# cdh.net
KiCad netlist of a schematic drawn in Altium Designer
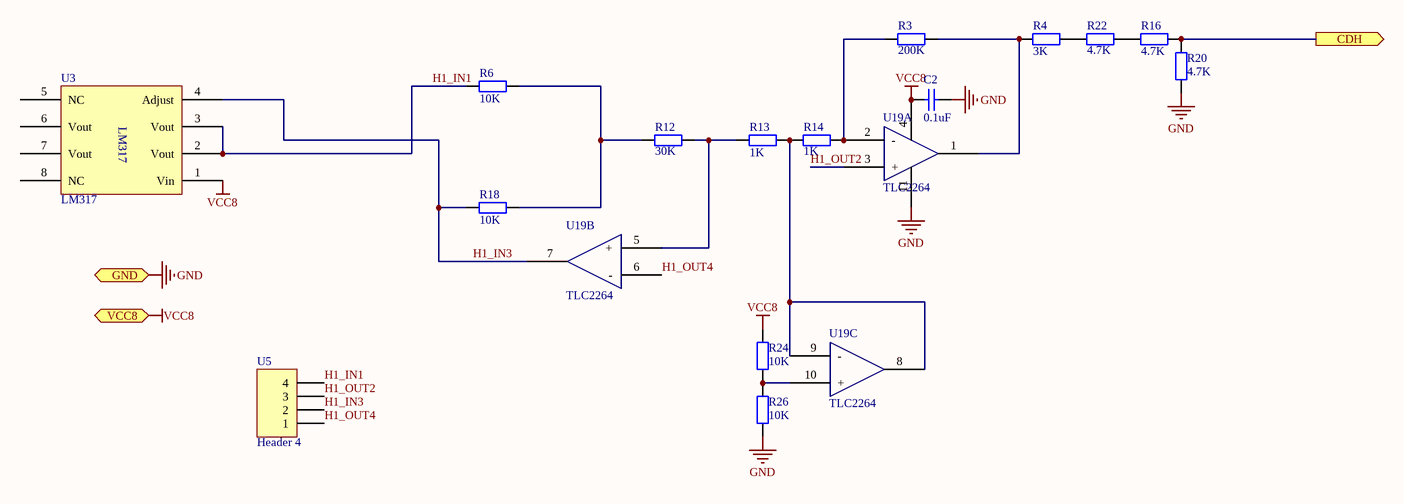
[diagram p0: cdh.SchDoc]

(export (version "E")
  (design (tool "Eeschema 10.0.6"))
  (components
    (comp (ref "C2")
      (value "0.1uF")
      (footprint "C0805")
      (description "Capacitor (Semiconductor SIM Model)")
      (fields (field (name "PUBLISHER") "Altium Limited"))
      (libsource (lib "Miscellaneous Devices") (part "Cap Semi"))
    )
    (comp (ref "R3")
      (value "200K")
      (footprint "0603_R")
      (description "Resistor")
      (fields (field (name "PUBLISHER") "Altium Limited"))
      (libsource (lib "") (part "Res2_1"))
    )
    (comp (ref "R4")
      (value "3K")
      (footprint "0603_R")
      (description "Resistor")
      (fields (field (name "PUBLISHER") "Altium Limited"))
      (libsource (lib "") (part "Res2_1"))
    )
    (comp (ref "R6")
      (value "10K")
      (footprint "0603_R")
      (description "Resistor")
      (fields (field (name "PUBLISHER") "Altium Limited"))
      (libsource (lib "") (part "Res2_1"))
    )
    (comp (ref "R12")
      (value "30K")
      (footprint "0603_R")
      (description "Resistor")
      (fields (field (name "PUBLISHER") "Altium Limited"))
      (libsource (lib "") (part "Res2_1"))
    )
    (comp (ref "R13")
      (value "1K")
      (footprint "0603_R")
      (description "Resistor")
      (fields (field (name "PUBLISHER") "Altium Limited"))
      (libsource (lib "") (part "Res2_1"))
    )
    (comp (ref "R14")
      (value "1K")
      (footprint "0603_R")
      (description "Resistor")
      (fields (field (name "PUBLISHER") "Altium Limited"))
      (libsource (lib "") (part "Res2_2"))
    )
    (comp (ref "R16")
      (value "4.7K")
      (footprint "0603_R")
      (description "Resistor")
      (fields (field (name "PUBLISHER") "Altium Limited"))
      (libsource (lib "") (part "Res2_1"))
    )
    (comp (ref "R18")
      (value "10K")
      (footprint "0603_R")
      (description "Resistor")
      (fields (field (name "PUBLISHER") "Altium Limited"))
      (libsource (lib "") (part "Res2_1"))
    )
    (comp (ref "R20")
      (value "4.7K")
      (footprint "0603_R")
      (description "Resistor")
      (fields (field (name "PUBLISHER") "Altium Limited"))
      (libsource (lib "Miscellaneous Devices") (part "Res2"))
    )
    (comp (ref "R22")
      (value "4.7K")
      (footprint "0603_R")
      (description "Resistor")
      (fields (field (name "PUBLISHER") "Altium Limited"))
      (libsource (lib "") (part "Res2_1"))
    )
    (comp (ref "R24")
      (value "10K")
      (footprint "0603_R")
      (description "Resistor")
      (fields (field (name "PUBLISHER") "Altium Limited"))
      (libsource (lib "Miscellaneous Devices") (part "Res2"))
    )
    (comp (ref "R26")
      (value "10K")
      (footprint "0603_R")
      (description "Resistor")
      (fields (field (name "PUBLISHER") "Altium Limited"))
      (libsource (lib "Miscellaneous Devices") (part "Res2"))
    )
    (comp (ref "U3") (value "LM317") (footprint "SO-8") (libsource (lib "磁导航") (part "LM317")))
    (comp (ref "U5")
      (value "Header 4")
      (footprint "PIN4")
      (description "Header, 4-Pin")
      (fields (field (name "PUBLISHER") "Altium Limited"))
      (libsource (lib "Miscellaneous Connectors") (part "Header 4"))
    )
    (comp (ref "U19") (value "TLC2264") (footprint "TSSOP14") (libsource (lib "EXPLORER") (part "TLC2264")))
  )
  (nets
    (net (code "1") (name "/CDH") (class "Default")
      (node (ref "R16") (pin "2") (pinfunction "2_2") (pintype "passive"))
      (node (ref "R20") (pin "2") (pinfunction "2_2") (pintype "passive"))
    )
    (net (code "2") (name "/H1_IN1") (class "Default")
      (node (ref "R6") (pin "1") (pinfunction "1_1") (pintype "passive"))
      (node (ref "U3") (pin "2") (pinfunction "Vout_2") (pintype "passive"))
      (node (ref "U3") (pin "3") (pinfunction "Vout_3") (pintype "passive"))
      (node (ref "U5") (pin "4") (pinfunction "4_4") (pintype "passive"))
    )
    (net (code "3") (name "/H1_IN3") (class "Default")
      (node (ref "R18") (pin "1") (pinfunction "1_1") (pintype "passive"))
      (node (ref "U19") (pin "7") (pinfunction "2OUT_7") (pintype "passive"))
      (node (ref "U3") (pin "4") (pinfunction "Adjust_4") (pintype "passive"))
      (node (ref "U5") (pin "2") (pinfunction "2_2") (pintype "passive"))
    )
    (net (code "4") (name "/H1_OUT2") (class "Default")
      (node (ref "U19") (pin "3") (pinfunction "+_3") (pintype "passive"))
      (node (ref "U5") (pin "3") (pinfunction "3_3") (pintype "passive"))
    )
    (net (code "5") (name "/H1_OUT4") (class "Default")
      (node (ref "U19") (pin "6") (pinfunction "-_6") (pintype "passive"))
      (node (ref "U5") (pin "1") (pinfunction "1_1") (pintype "passive"))
    )
    (net (code "6") (name "GND") (class "Default")
      (node (ref "C2") (pin "1") (pinfunction "1_1") (pintype "passive"))
      (node (ref "R20") (pin "1") (pinfunction "1_1") (pintype "passive"))
      (node (ref "R26") (pin "1") (pinfunction "1_1") (pintype "passive"))
      (node (ref "U19") (pin "11") (pinfunction "GND_11") (pintype "passive"))
    )
    (net (code "7") (name "Net-(R12-Pad1)") (class "Default")
      (node (ref "R12") (pin "1") (pinfunction "1_1") (pintype "passive"))
      (node (ref "R18") (pin "2") (pinfunction "2_2") (pintype "passive"))
      (node (ref "R6") (pin "2") (pinfunction "2_2") (pintype "passive"))
    )
    (net (code "8") (name "Net-(R16-Pad1)") (class "Default")
      (node (ref "R16") (pin "1") (pinfunction "1_1") (pintype "passive"))
      (node (ref "R22") (pin "2") (pinfunction "2_2") (pintype "passive"))
    )
    (net (code "9") (name "Net-(R22-Pad1)") (class "Default")
      (node (ref "R22") (pin "1") (pinfunction "1_1") (pintype "passive"))
      (node (ref "R4") (pin "2") (pinfunction "2_2") (pintype "passive"))
    )
    (net (code "10") (name "Net-(U19A--)") (class "Default")
      (node (ref "R14") (pin "1") (pinfunction "1_1") (pintype "passive"))
      (node (ref "R3") (pin "1") (pinfunction "1_1") (pintype "passive"))
      (node (ref "U19") (pin "2") (pinfunction "-_2") (pintype "passive"))
    )
    (net (code "11") (name "Net-(U19A-1OUT)") (class "Default")
      (node (ref "R3") (pin "2") (pinfunction "2_2") (pintype "passive"))
      (node (ref "R4") (pin "1") (pinfunction "1_1") (pintype "passive"))
      (node (ref "U19") (pin "1") (pinfunction "1OUT_1") (pintype "passive"))
    )
    (net (code "12") (name "Net-(U19B-+)") (class "Default")
      (node (ref "R12") (pin "2") (pinfunction "2_2") (pintype "passive"))
      (node (ref "R13") (pin "1") (pinfunction "1_1") (pintype "passive"))
      (node (ref "U19") (pin "5") (pinfunction "+_5") (pintype "passive"))
    )
    (net (code "13") (name "Net-(U19C-+)") (class "Default")
      (node (ref "R24") (pin "1") (pinfunction "1_1") (pintype "passive"))
      (node (ref "R26") (pin "2") (pinfunction "2_2") (pintype "passive"))
      (node (ref "U19") (pin "10") (pinfunction "+_10") (pintype "passive"))
    )
    (net (code "14") (name "Net-(U19C--)") (class "Default")
      (node (ref "R13") (pin "2") (pinfunction "2_2") (pintype "passive"))
      (node (ref "R14") (pin "2") (pinfunction "2_2") (pintype "passive"))
      (node (ref "U19") (pin "8") (pinfunction "3OUT_8") (pintype "passive"))
      (node (ref "U19") (pin "9") (pinfunction "-_9") (pintype "passive"))
    )
    (net (code "15") (name "VCC8") (class "Default")
      (node (ref "C2") (pin "2") (pinfunction "2_2") (pintype "passive"))
      (node (ref "R24") (pin "2") (pinfunction "2_2") (pintype "passive"))
      (node (ref "U19") (pin "4") (pinfunction "VCC_4") (pintype "passive"))
      (node (ref "U3") (pin "1") (pinfunction "Vin_1") (pintype "passive"))
    )
    (net (code "16") (name "unconnected-(U3-NC-Pad5)") (class "Default")
      (node (ref "U3") (pin "5") (pinfunction "NC_5") (pintype "passive"))
    )
    (net (code "17") (name "unconnected-(U3-NC-Pad8)") (class "Default")
      (node (ref "U3") (pin "8") (pinfunction "NC_8") (pintype "passive"))
    )
    (net (code "18") (name "unconnected-(U3-Vout-Pad6)") (class "Default")
      (node (ref "U3") (pin "6") (pinfunction "Vout_6") (pintype "passive"))
    )
    (net (code "19") (name "unconnected-(U3-Vout-Pad7)") (class "Default")
      (node (ref "U3") (pin "7") (pinfunction "Vout_7") (pintype "passive"))
    )
  )
)
